# Core.net
KiCad netlist of a schematic drawn in Altium Designer
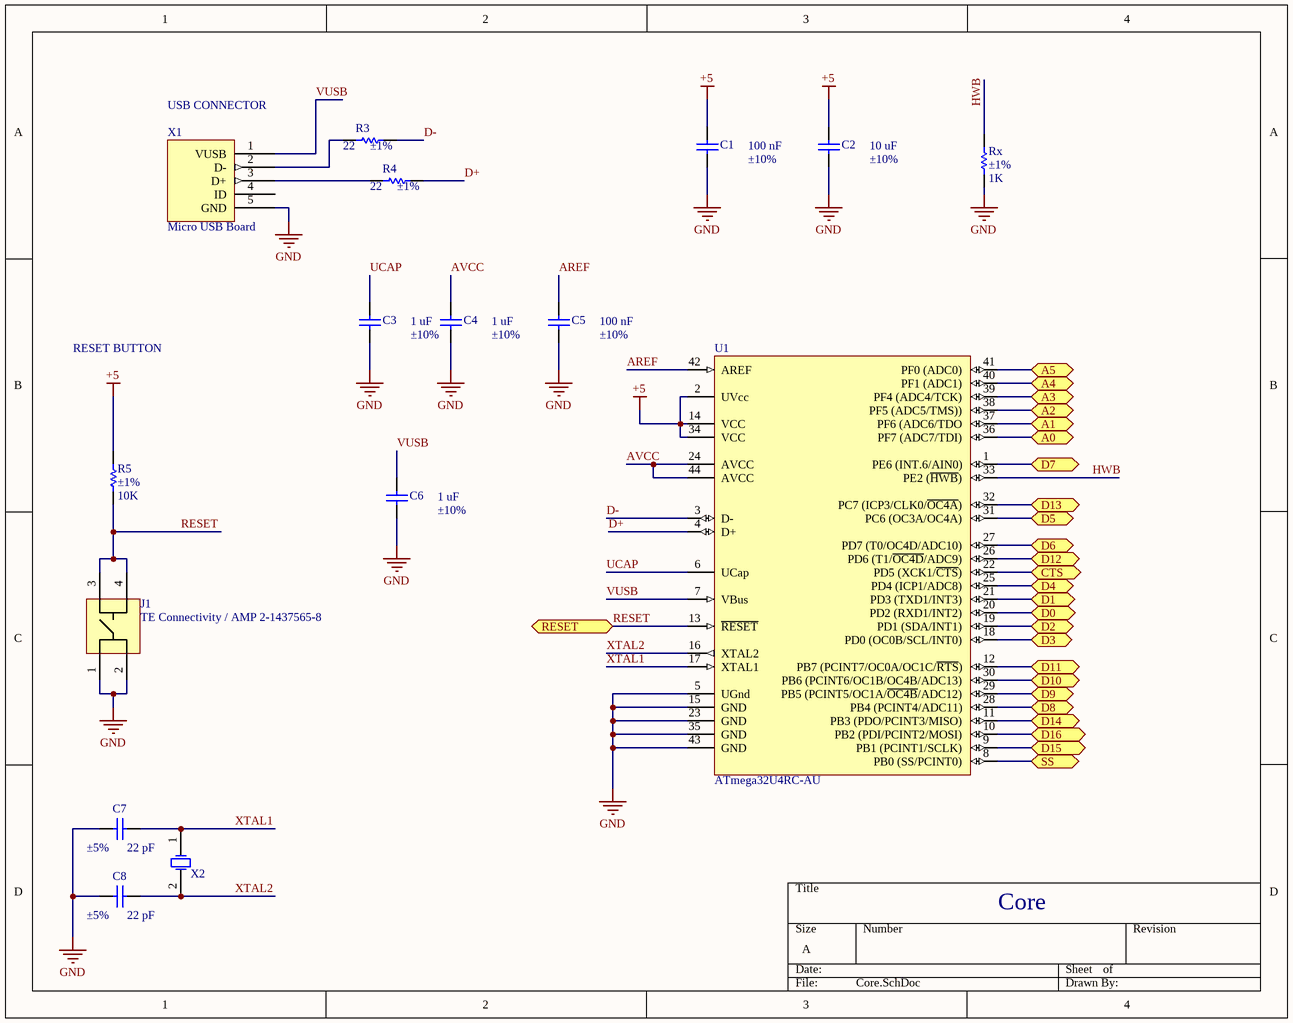
[diagram p0: Core.SchDoc]

(export (version "E")
  (design (tool "Eeschema 10.0.6"))
  (components
    (comp (ref "C1")
      (value "Taiyo Yuden LMK212BJ106KG-T")
      (footprint "PCB-i747o4qnz4fc2aqkwc14-1")
      (description "Cap Ceramic 10uF 10V X5R 10% SMD 0805 85?C T/R")
      (fields
        (field (name "MANUFACTURER PART NUMBER") "LMK212BJ106KG-T")
        (field (name "CAPACITANCE") "100 nF")
        (field (name "CAPACITANCE TOLERANCE") "±10%")
      )
      (libsource (lib "CommunityVault") (part "CMP-6ecba7c24c09b10c-2"))
    )
    (comp (ref "C2")
      (value "Taiyo Yuden LMK212BJ106KG-T")
      (footprint "PCB-i747o4qnz4fc2aqkwc14-1")
      (description "Cap Ceramic 10uF 10V X5R 10% SMD 0805 85?C T/R")
      (fields
        (field (name "MANUFACTURER PART NUMBER") "LMK212BJ106KG-T")
        (field (name "CAPACITANCE") "10 uF")
        (field (name "CAPACITANCE TOLERANCE") "±10%")
      )
      (libsource (lib "CommunityVault") (part "CMP-6ecba7c24c09b10c-2"))
    )
    (comp (ref "C3")
      (value "Taiyo Yuden LMK212BJ106KG-T")
      (footprint "PCB-i747o4qnz4fc2aqkwc14-1")
      (description "Cap Ceramic 10uF 10V X5R 10% SMD 0805 85?C T/R")
      (fields
        (field (name "MANUFACTURER PART NUMBER") "LMK212BJ106KG-T")
        (field (name "CAPACITANCE") "1 uF")
        (field (name "CAPACITANCE TOLERANCE") "±10%")
      )
      (libsource (lib "CommunityVault") (part "CMP-6ecba7c24c09b10c-2"))
    )
    (comp (ref "C4")
      (value "Taiyo Yuden LMK212BJ106KG-T")
      (footprint "PCB-i747o4qnz4fc2aqkwc14-1")
      (description "Cap Ceramic 10uF 10V X5R 10% SMD 0805 85?C T/R")
      (fields
        (field (name "MANUFACTURER PART NUMBER") "LMK212BJ106KG-T")
        (field (name "CAPACITANCE") "1 uF")
        (field (name "CAPACITANCE TOLERANCE") "±10%")
      )
      (libsource (lib "CommunityVault") (part "CMP-6ecba7c24c09b10c-2"))
    )
    (comp (ref "C5")
      (value "Taiyo Yuden LMK212BJ106KG-T")
      (footprint "PCB-i747o4qnz4fc2aqkwc14-1")
      (description "Cap Ceramic 10uF 10V X5R 10% SMD 0805 85?C T/R")
      (fields
        (field (name "MANUFACTURER PART NUMBER") "LMK212BJ106KG-T")
        (field (name "CAPACITANCE") "100 nF")
        (field (name "CAPACITANCE TOLERANCE") "±10%")
      )
      (libsource (lib "CommunityVault") (part "CMP-6ecba7c24c09b10c-2"))
    )
    (comp (ref "C6")
      (value "Taiyo Yuden LMK212BJ106KG-T")
      (footprint "PCB-i747o4qnz4fc2aqkwc14-1")
      (description "Cap Ceramic 10uF 10V X5R 10% SMD 0805 85?C T/R")
      (fields
        (field (name "MANUFACTURER PART NUMBER") "LMK212BJ106KG-T")
        (field (name "CAPACITANCE") "1 uF")
        (field (name "CAPACITANCE TOLERANCE") "±10%")
      )
      (libsource (lib "CommunityVault") (part "CMP-6ecba7c24c09b10c-2"))
    )
    (comp (ref "C7")
      (value "Taiyo Yuden LMK212BJ106KG-T")
      (footprint "PCB-i747o4qnz4fc2aqkwc14-1")
      (description "Cap Ceramic 10uF 10V X5R 10% SMD 0805 85?C T/R")
      (fields
        (field (name "MANUFACTURER PART NUMBER") "LMK212BJ106KG-T")
        (field (name "CAPACITANCE") "22 pF")
        (field (name "CAPACITANCE TOLERANCE") "±5%")
      )
      (libsource (lib "CommunityVault") (part "CMP-6ecba7c24c09b10c-2"))
    )
    (comp (ref "C8")
      (value "Taiyo Yuden LMK212BJ106KG-T")
      (footprint "PCB-i747o4qnz4fc2aqkwc14-1")
      (description "Cap Ceramic 10uF 10V X5R 10% SMD 0805 85?C T/R")
      (fields
        (field (name "MANUFACTURER PART NUMBER") "LMK212BJ106KG-T")
        (field (name "CAPACITANCE") "22 pF")
        (field (name "CAPACITANCE TOLERANCE") "±5%")
      )
      (libsource (lib "CommunityVault") (part "CMP-6ecba7c24c09b10c-2"))
    )
    (comp (ref "J1")
      (value "TE Connectivity / AMP 2-1437565-8")
      (footprint "PCB-70k6oqbhuv68f7gyhifn-1")
      (description "Switch Tactile OFF (ON) SPST Round Button Gull Wing 0.05A 12VDC 2.55N SMD Loose Piece")
      (fields (field (name "MANUFACTURER PART NUMBER") "2-1437565-8"))
      (libsource (lib "Octopart library") (part "SYM-fb7e300dae6a24b9-1"))
    )
    (comp (ref "R3")
      (value "Bourns CR0805-FX-4701GLF")
      (footprint "PCB-4097432-1")
      (description "Res Thick Film 0805 4.7K Ohm 1% 1/8W ±100ppm/°C Molded SMD SMD Paper Tape on Plastic Reel")
      (fields
        (field (name "MANUFACTURER PART NUMBER") "CR0805-FX-4701GLF")
        (field (name "RESISTANCE TOLERANCE") "±1%")
        (field (name "RESISTANCE") "22")
      )
      (libsource (lib "CommunityVault") (part "CMP-97505e06006c4897-1"))
    )
    (comp (ref "R4")
      (value "Bourns CR0805-FX-4701GLF")
      (footprint "PCB-4097432-1")
      (description "Res Thick Film 0805 4.7K Ohm 1% 1/8W ±100ppm/°C Molded SMD SMD Paper Tape on Plastic Reel")
      (fields
        (field (name "MANUFACTURER PART NUMBER") "CR0805-FX-4701GLF")
        (field (name "RESISTANCE TOLERANCE") "±1%")
        (field (name "RESISTANCE") "22")
      )
      (libsource (lib "CommunityVault") (part "CMP-97505e06006c4897-1"))
    )
    (comp (ref "R5")
      (value "Bourns CR0805-FX-4701GLF")
      (footprint "PCB-4097432-1")
      (description "Res Thick Film 0805 4.7K Ohm 1% 1/8W ±100ppm/°C Molded SMD SMD Paper Tape on Plastic Reel")
      (fields
        (field (name "MANUFACTURER PART NUMBER") "CR0805-FX-4701GLF")
        (field (name "RESISTANCE TOLERANCE") "±1%")
        (field (name "RESISTANCE") "10K")
      )
      (libsource (lib "CommunityVault") (part "CMP-97505e06006c4897-1"))
    )
    (comp (ref "Rx")
      (value "Bourns CR0805-FX-4701GLF")
      (footprint "PCB-4097432-1")
      (description "Res Thick Film 0805 4.7K Ohm 1% 1/8W ±100ppm/°C Molded SMD SMD Paper Tape on Plastic Reel")
      (fields
        (field (name "MANUFACTURER PART NUMBER") "CR0805-FX-4701GLF")
        (field (name "RESISTANCE TOLERANCE") "±1%")
        (field (name "RESISTANCE") "1K")
      )
      (libsource (lib "CommunityVault") (part "CMP-97505e06006c4897-1"))
    )
    (comp (ref "U1")
      (value "ATmega32U4RC-AU")
      (footprint "44ML_L")
      (fields (field (name "MANUFACTURER") "Atmel"))
      (libsource (lib "Octopart library") (part "MC-8B-ATM16U4-SQ44"))
    )
    (comp (ref "X1")
      (value "Micro USB Board")
      (footprint "PCB-y0d6oczsv3eu57ue5a53-1")
      (libsource (lib "CommunityVault") (part "CMP-dryhiu0utvtqwfw1f267-2"))
    )
    (comp (ref "X2")
      (value "Fox Electronics FOXSDLF/160-20")
      (footprint "FOX-FOXSDLF-160-20")
      (description "CRYSTAL 16.0MHZ 20PF SMD")
      (libsource (lib "CommunityVault") (part "CMP-779572-4"))
    )
  )
  (nets
    (net (code "1") (name "+5") (class "Default")
      (node (ref "C1") (pin "2") (pinfunction "2_2") (pintype "passive"))
      (node (ref "C2") (pin "2") (pinfunction "2_2") (pintype "passive"))
      (node (ref "R5") (pin "2") (pinfunction "2_2") (pintype "passive"))
      (node (ref "U1") (pin "14") (pinfunction "VCC_14") (pintype "power_in"))
      (node (ref "U1") (pin "2") (pinfunction "UVcc_2") (pintype "power_in"))
      (node (ref "U1") (pin "34") (pinfunction "VCC_34") (pintype "power_in"))
    )
    (net (code "2") (name "/A0") (class "Default")
      (node (ref "U1") (pin "36") (pinfunction "PF7_(ADC7/TDI)_36") (pintype "bidirectional"))
    )
    (net (code "3") (name "/A1") (class "Default")
      (node (ref "U1") (pin "37") (pinfunction "PF6_(ADC6/TDO_37") (pintype "bidirectional"))
    )
    (net (code "4") (name "/A2") (class "Default")
      (node (ref "U1") (pin "38") (pinfunction "PF5_(ADC5/TMS))_38") (pintype "bidirectional"))
    )
    (net (code "5") (name "/A3") (class "Default")
      (node (ref "U1") (pin "39") (pinfunction "PF4_(ADC4/TCK)_39") (pintype "bidirectional"))
    )
    (net (code "6") (name "/A4") (class "Default")
      (node (ref "U1") (pin "40") (pinfunction "PF1_(ADC1)_40") (pintype "bidirectional"))
    )
    (net (code "7") (name "/A5") (class "Default")
      (node (ref "U1") (pin "41") (pinfunction "PF0_(ADC0)_41") (pintype "bidirectional"))
    )
    (net (code "8") (name "/AREF") (class "Default")
      (node (ref "C5") (pin "2") (pinfunction "2_2") (pintype "passive"))
      (node (ref "U1") (pin "42") (pinfunction "AREF_42") (pintype "input"))
    )
    (net (code "9") (name "/AVCC") (class "Default")
      (node (ref "C4") (pin "2") (pinfunction "2_2") (pintype "passive"))
      (node (ref "U1") (pin "24") (pinfunction "AVCC_24") (pintype "power_in"))
      (node (ref "U1") (pin "44") (pinfunction "AVCC_44") (pintype "power_in"))
    )
    (net (code "10") (name "/CTS") (class "Default")
      (node (ref "U1") (pin "22") (pinfunction "PD5_(XCK1/~{CTS})_22") (pintype "bidirectional"))
    )
    (net (code "11") (name "/D+") (class "Default")
      (node (ref "R4") (pin "2") (pinfunction "2_2") (pintype "passive"))
      (node (ref "U1") (pin "4") (pinfunction "D+_4") (pintype "bidirectional"))
    )
    (net (code "12") (name "/D-") (class "Default")
      (node (ref "R3") (pin "2") (pinfunction "2_2") (pintype "passive"))
      (node (ref "U1") (pin "3") (pinfunction "D-_3") (pintype "bidirectional"))
    )
    (net (code "13") (name "/D0") (class "Default")
      (node (ref "U1") (pin "20") (pinfunction "PD2_(RXD1/INT2)_20") (pintype "bidirectional"))
    )
    (net (code "14") (name "/D1") (class "Default")
      (node (ref "U1") (pin "21") (pinfunction "PD3_(TXD1/INT3)_21") (pintype "bidirectional"))
    )
    (net (code "15") (name "/D2") (class "Default")
      (node (ref "U1") (pin "19") (pinfunction "PD1_(SDA/INT1)_19") (pintype "bidirectional"))
    )
    (net (code "16") (name "/D3") (class "Default")
      (node (ref "U1") (pin "18") (pinfunction "PD0_(OC0B/SCL/INT0)_18") (pintype "bidirectional"))
    )
    (net (code "17") (name "/D4") (class "Default")
      (node (ref "U1") (pin "25") (pinfunction "PD4_(ICP1/ADC8)_25") (pintype "bidirectional"))
    )
    (net (code "18") (name "/D5") (class "Default")
      (node (ref "U1") (pin "31") (pinfunction "PC6_(OC3A/OC4A)_31") (pintype "bidirectional"))
    )
    (net (code "19") (name "/D6") (class "Default")
      (node (ref "U1") (pin "27") (pinfunction "PD7_(T0/OC4D/ADC10)_27") (pintype "bidirectional"))
    )
    (net (code "20") (name "/D7") (class "Default")
      (node (ref "U1") (pin "1") (pinfunction "PE6_(INT.6/AIN0)_1") (pintype "bidirectional"))
    )
    (net (code "21") (name "/D8") (class "Default")
      (node (ref "U1") (pin "28") (pinfunction "PB4_(PCINT4/ADC11)_28") (pintype "bidirectional"))
    )
    (net (code "22") (name "/D9") (class "Default")
      (node (ref "U1") (pin "29") (pinfunction "PB5_(PCINT5/OC1A/~{OC4B}/ADC12)_29") (pintype "bidirectional"))
    )
    (net (code "23") (name "/D10") (class "Default")
      (node (ref "U1") (pin "30") (pinfunction "PB6_(PCINT6/OC1B/OC4B/ADC13)_30") (pintype "bidirectional"))
    )
    (net (code "24") (name "/D11") (class "Default")
      (node (ref "U1") (pin "12") (pinfunction "PB7_(PCINT7/OC0A/OC1C/~{RTS})_12") (pintype "bidirectional"))
    )
    (net (code "25") (name "/D12") (class "Default")
      (node (ref "U1") (pin "26") (pinfunction "PD6_(T1/~{OC4D}/ADC9)_26") (pintype "bidirectional"))
    )
    (net (code "26") (name "/D13") (class "Default")
      (node (ref "U1") (pin "32") (pinfunction "PC7_(ICP3/CLK0/~{OC4A})_32") (pintype "bidirectional"))
    )
    (net (code "27") (name "/D14") (class "Default")
      (node (ref "U1") (pin "11") (pinfunction "PB3_(PDO/PCINT3/MISO)_11") (pintype "bidirectional"))
    )
    (net (code "28") (name "/D15") (class "Default")
      (node (ref "U1") (pin "9") (pinfunction "PB1_(PCINT1/SCLK)_9") (pintype "bidirectional"))
    )
    (net (code "29") (name "/D16") (class "Default")
      (node (ref "U1") (pin "10") (pinfunction "PB2_(PDI/PCINT2/MOSI)_10") (pintype "bidirectional"))
    )
    (net (code "30") (name "/HWB") (class "Default")
      (node (ref "Rx") (pin "2") (pinfunction "2_2") (pintype "passive"))
      (node (ref "U1") (pin "33") (pinfunction "PE2_(~{HWB})_33") (pintype "bidirectional"))
    )
    (net (code "31") (name "/RESET") (class "Default")
      (node (ref "J1") (pin "3") (pinfunction "3_3") (pintype "passive"))
      (node (ref "J1") (pin "4") (pinfunction "4_4") (pintype "passive"))
      (node (ref "R5") (pin "1") (pinfunction "1_1") (pintype "passive"))
      (node (ref "U1") (pin "13") (pinfunction "~{RESET}_13") (pintype "input"))
    )
    (net (code "32") (name "/SS") (class "Default")
      (node (ref "U1") (pin "8") (pinfunction "PB0_(SS/PCINT0)_8") (pintype "bidirectional"))
    )
    (net (code "33") (name "/UCAP") (class "Default")
      (node (ref "C3") (pin "2") (pinfunction "2_2") (pintype "passive"))
      (node (ref "U1") (pin "6") (pinfunction "UCap_6") (pintype "passive"))
    )
    (net (code "34") (name "/VUSB") (class "Default")
      (node (ref "C6") (pin "2") (pinfunction "2_2") (pintype "passive"))
      (node (ref "U1") (pin "7") (pinfunction "VBus_7") (pintype "input"))
      (node (ref "X1") (pin "1") (pinfunction "VUSB_1") (pintype "power_in"))
    )
    (net (code "35") (name "/XTAL1") (class "Default")
      (node (ref "C7") (pin "2") (pinfunction "2_2") (pintype "passive"))
      (node (ref "U1") (pin "17") (pinfunction "XTAL1_17") (pintype "input"))
      (node (ref "X2") (pin "1") (pinfunction "OSC1_1") (pintype "passive"))
    )
    (net (code "36") (name "/XTAL2") (class "Default")
      (node (ref "C8") (pin "2") (pinfunction "2_2") (pintype "passive"))
      (node (ref "U1") (pin "16") (pinfunction "XTAL2_16") (pintype "output"))
      (node (ref "X2") (pin "2") (pinfunction "OSC2_2") (pintype "passive"))
    )
    (net (code "37") (name "GND") (class "Default")
      (node (ref "C1") (pin "1") (pinfunction "1_1") (pintype "passive"))
      (node (ref "C2") (pin "1") (pinfunction "1_1") (pintype "passive"))
      (node (ref "C3") (pin "1") (pinfunction "1_1") (pintype "passive"))
      (node (ref "C4") (pin "1") (pinfunction "1_1") (pintype "passive"))
      (node (ref "C5") (pin "1") (pinfunction "1_1") (pintype "passive"))
      (node (ref "C6") (pin "1") (pinfunction "1_1") (pintype "passive"))
      (node (ref "C7") (pin "1") (pinfunction "1_1") (pintype "passive"))
      (node (ref "C8") (pin "1") (pinfunction "1_1") (pintype "passive"))
      (node (ref "J1") (pin "1") (pinfunction "1_1") (pintype "passive"))
      (node (ref "J1") (pin "2") (pinfunction "2_2") (pintype "passive"))
      (node (ref "Rx") (pin "1") (pinfunction "1_1") (pintype "passive"))
      (node (ref "U1") (pin "15") (pinfunction "GND_15") (pintype "power_in"))
      (node (ref "U1") (pin "23") (pinfunction "GND_23") (pintype "power_in"))
      (node (ref "U1") (pin "35") (pinfunction "GND_35") (pintype "power_in"))
      (node (ref "U1") (pin "43") (pinfunction "GND_43") (pintype "power_in"))
      (node (ref "U1") (pin "5") (pinfunction "UGnd_5") (pintype "power_in"))
      (node (ref "X1") (pin "5") (pinfunction "GND_5") (pintype "power_in"))
    )
    (net (code "38") (name "Net-(X1-D+)") (class "Default")
      (node (ref "R4") (pin "1") (pinfunction "1_1") (pintype "passive"))
      (node (ref "X1") (pin "3") (pinfunction "D+_3") (pintype "output"))
    )
    (net (code "39") (name "Net-(X1-D-)") (class "Default")
      (node (ref "R3") (pin "1") (pinfunction "1_1") (pintype "passive"))
      (node (ref "X1") (pin "2") (pinfunction "D-_2") (pintype "output"))
    )
    (net (code "40") (name "unconnected-(X1-ID-Pad4)") (class "Default")
      (node (ref "X1") (pin "4") (pinfunction "ID_4") (pintype "passive"))
    )
  )
)
